# Sensor.net
KiCad netlist of a schematic drawn in Altium Designer
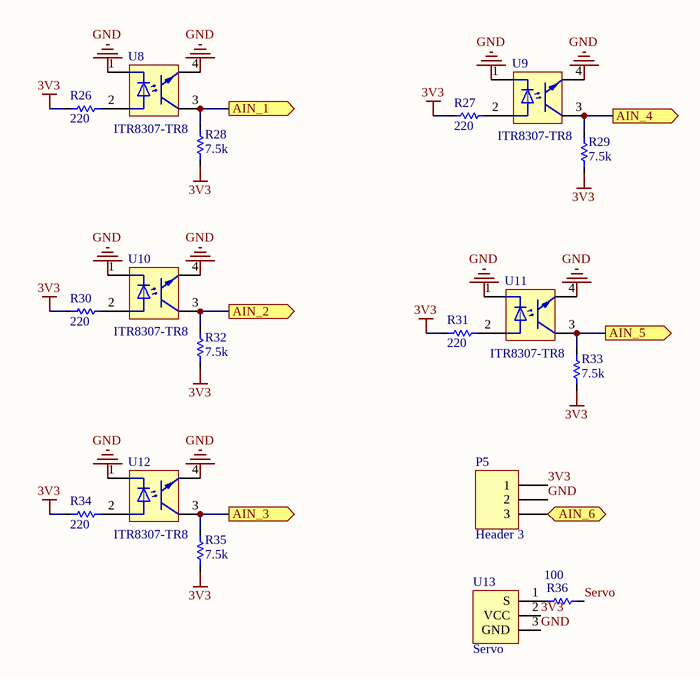
[diagram p0: Sensor.SchDoc]

(export (version "E")
  (design (tool "Eeschema 10.0.6"))
  (components
    (comp (ref "P5")
      (value "Header 3")
      (footprint "A1.25WF-3P")
      (description "Header, 3-Pin")
      (fields (field (name "PUBLISHER") "Altium Limited"))
      (libsource (lib "Miscellaneous Connectors") (part "Header 3"))
    )
    (comp (ref "R26")
      (value "220")
      (footprint "0603R")
      (description "Resistor")
      (fields (field (name "PUBLISHER") "Altium Limited"))
      (libsource (lib "OurSuperMiniCar") (part "Res1"))
    )
    (comp (ref "R27")
      (value "220")
      (footprint "0603R")
      (description "Resistor")
      (fields (field (name "PUBLISHER") "Altium Limited"))
      (libsource (lib "OurSuperMiniCar") (part "Res1"))
    )
    (comp (ref "R28")
      (value "7.5k")
      (footprint "0603R")
      (description "Resistor")
      (fields (field (name "PUBLISHER") "Altium Limited"))
      (libsource (lib "OurSuperMiniCar") (part "Res1"))
    )
    (comp (ref "R29")
      (value "7.5k")
      (footprint "0603R")
      (description "Resistor")
      (fields (field (name "PUBLISHER") "Altium Limited"))
      (libsource (lib "OurSuperMiniCar") (part "Res1"))
    )
    (comp (ref "R30")
      (value "220")
      (footprint "0603R")
      (description "Resistor")
      (fields (field (name "PUBLISHER") "Altium Limited"))
      (libsource (lib "OurSuperMiniCar") (part "Res1"))
    )
    (comp (ref "R31")
      (value "220")
      (footprint "0603R")
      (description "Resistor")
      (fields (field (name "PUBLISHER") "Altium Limited"))
      (libsource (lib "OurSuperMiniCar") (part "Res1"))
    )
    (comp (ref "R32")
      (value "7.5k")
      (footprint "0603R")
      (description "Resistor")
      (fields (field (name "PUBLISHER") "Altium Limited"))
      (libsource (lib "OurSuperMiniCar") (part "Res1"))
    )
    (comp (ref "R33")
      (value "7.5k")
      (footprint "0603R")
      (description "Resistor")
      (fields (field (name "PUBLISHER") "Altium Limited"))
      (libsource (lib "OurSuperMiniCar") (part "Res1"))
    )
    (comp (ref "R34")
      (value "220")
      (footprint "0603R")
      (description "Resistor")
      (fields (field (name "PUBLISHER") "Altium Limited"))
      (libsource (lib "OurSuperMiniCar") (part "Res1"))
    )
    (comp (ref "R35")
      (value "7.5k")
      (footprint "0603R")
      (description "Resistor")
      (fields (field (name "PUBLISHER") "Altium Limited"))
      (libsource (lib "OurSuperMiniCar") (part "Res1"))
    )
    (comp (ref "R36")
      (value "100")
      (footprint "0603R")
      (description "Resistor")
      (fields (field (name "Comment") "1K/5%") (field (name "PUBLISHER") "Altium Limited"))
      (libsource (lib "OurSuperMiniCar") (part "Res1"))
    )
    (comp (ref "U8")
      (value "ITR8307-TR8")
      (footprint "SOP-4")
      (libsource (lib "OurSuperMiniCar") (part "ITR8307-TR8"))
    )
    (comp (ref "U9")
      (value "ITR8307-TR8")
      (footprint "SOP-4")
      (libsource (lib "OurSuperMiniCar") (part "ITR8307-TR8"))
    )
    (comp (ref "U10")
      (value "ITR8307-TR8")
      (footprint "SOP-4")
      (libsource (lib "OurSuperMiniCar") (part "ITR8307-TR8"))
    )
    (comp (ref "U11")
      (value "ITR8307-TR8")
      (footprint "SOP-4")
      (libsource (lib "OurSuperMiniCar") (part "ITR8307-TR8"))
    )
    (comp (ref "U12")
      (value "ITR8307-TR8")
      (footprint "SOP-4")
      (libsource (lib "OurSuperMiniCar") (part "ITR8307-TR8"))
    )
    (comp (ref "U13") (value "Servo") (footprint "HDR1X3") (libsource (lib "OurSuperMiniCar") (part "Servo")))
  )
  (nets
    (net (code "1") (name "/AIN_1") (class "Default")
      (node (ref "R28") (pin "1") (pinfunction "1_1") (pintype "passive"))
      (node (ref "U8") (pin "3") (pinfunction "COLLECTER_3") (pintype "open_collector"))
    )
    (net (code "2") (name "/AIN_2") (class "Default")
      (node (ref "R32") (pin "1") (pinfunction "1_1") (pintype "passive"))
      (node (ref "U10") (pin "3") (pinfunction "COLLECTER_3") (pintype "open_collector"))
    )
    (net (code "3") (name "/AIN_3") (class "Default")
      (node (ref "R35") (pin "1") (pinfunction "1_1") (pintype "passive"))
      (node (ref "U12") (pin "3") (pinfunction "COLLECTER_3") (pintype "open_collector"))
    )
    (net (code "4") (name "/AIN_4") (class "Default")
      (node (ref "R29") (pin "1") (pinfunction "1_1") (pintype "passive"))
      (node (ref "U9") (pin "3") (pinfunction "COLLECTER_3") (pintype "open_collector"))
    )
    (net (code "5") (name "/AIN_5") (class "Default")
      (node (ref "R33") (pin "1") (pinfunction "1_1") (pintype "passive"))
      (node (ref "U11") (pin "3") (pinfunction "COLLECTER_3") (pintype "open_collector"))
    )
    (net (code "6") (name "/AIN_6") (class "Default")
      (node (ref "P5") (pin "3") (pinfunction "3_3") (pintype "passive"))
    )
    (net (code "7") (name "/Servo") (class "Default")
      (node (ref "R36") (pin "1") (pinfunction "1_1") (pintype "passive"))
    )
    (net (code "8") (name "3V3") (class "Default")
      (node (ref "P5") (pin "1") (pinfunction "1_1") (pintype "passive"))
      (node (ref "R26") (pin "2") (pinfunction "2_2") (pintype "passive"))
      (node (ref "R27") (pin "2") (pinfunction "2_2") (pintype "passive"))
      (node (ref "R28") (pin "2") (pinfunction "2_2") (pintype "passive"))
      (node (ref "R29") (pin "2") (pinfunction "2_2") (pintype "passive"))
      (node (ref "R30") (pin "2") (pinfunction "2_2") (pintype "passive"))
      (node (ref "R31") (pin "2") (pinfunction "2_2") (pintype "passive"))
      (node (ref "R32") (pin "2") (pinfunction "2_2") (pintype "passive"))
      (node (ref "R33") (pin "2") (pinfunction "2_2") (pintype "passive"))
      (node (ref "R34") (pin "2") (pinfunction "2_2") (pintype "passive"))
      (node (ref "R35") (pin "2") (pinfunction "2_2") (pintype "passive"))
      (node (ref "U13") (pin "2") (pinfunction "VCC_2") (pintype "open_collector"))
    )
    (net (code "9") (name "GND") (class "Default")
      (node (ref "P5") (pin "2") (pinfunction "2_2") (pintype "passive"))
      (node (ref "U10") (pin "1") (pinfunction "CATHODE_1") (pintype "open_collector"))
      (node (ref "U10") (pin "4") (pinfunction "EMITTER_4") (pintype "open_collector"))
      (node (ref "U11") (pin "1") (pinfunction "CATHODE_1") (pintype "open_collector"))
      (node (ref "U11") (pin "4") (pinfunction "EMITTER_4") (pintype "open_collector"))
      (node (ref "U12") (pin "1") (pinfunction "CATHODE_1") (pintype "open_collector"))
      (node (ref "U12") (pin "4") (pinfunction "EMITTER_4") (pintype "open_collector"))
      (node (ref "U13") (pin "3") (pinfunction "GND_3") (pintype "open_collector"))
      (node (ref "U8") (pin "1") (pinfunction "CATHODE_1") (pintype "open_collector"))
      (node (ref "U8") (pin "4") (pinfunction "EMITTER_4") (pintype "open_collector"))
      (node (ref "U9") (pin "1") (pinfunction "CATHODE_1") (pintype "open_collector"))
      (node (ref "U9") (pin "4") (pinfunction "EMITTER_4") (pintype "open_collector"))
    )
    (net (code "10") (name "Net-(U8-ANODE)") (class "Default")
      (node (ref "R26") (pin "1") (pinfunction "1_1") (pintype "passive"))
      (node (ref "U8") (pin "2") (pinfunction "ANODE_2") (pintype "open_collector"))
    )
    (net (code "11") (name "Net-(U9-ANODE)") (class "Default")
      (node (ref "R27") (pin "1") (pinfunction "1_1") (pintype "passive"))
      (node (ref "U9") (pin "2") (pinfunction "ANODE_2") (pintype "open_collector"))
    )
    (net (code "12") (name "Net-(U10-ANODE)") (class "Default")
      (node (ref "R30") (pin "1") (pinfunction "1_1") (pintype "passive"))
      (node (ref "U10") (pin "2") (pinfunction "ANODE_2") (pintype "open_collector"))
    )
    (net (code "13") (name "Net-(U11-ANODE)") (class "Default")
      (node (ref "R31") (pin "1") (pinfunction "1_1") (pintype "passive"))
      (node (ref "U11") (pin "2") (pinfunction "ANODE_2") (pintype "open_collector"))
    )
    (net (code "14") (name "Net-(U12-ANODE)") (class "Default")
      (node (ref "R34") (pin "1") (pinfunction "1_1") (pintype "passive"))
      (node (ref "U12") (pin "2") (pinfunction "ANODE_2") (pintype "open_collector"))
    )
    (net (code "15") (name "Net-(U13-S)") (class "Default")
      (node (ref "R36") (pin "2") (pinfunction "2_2") (pintype "passive"))
      (node (ref "U13") (pin "1") (pinfunction "S_1") (pintype "open_collector"))
    )
  )
)
